# EASYEDA.net
KiCad netlist of a schematic drawn in EasyEDA
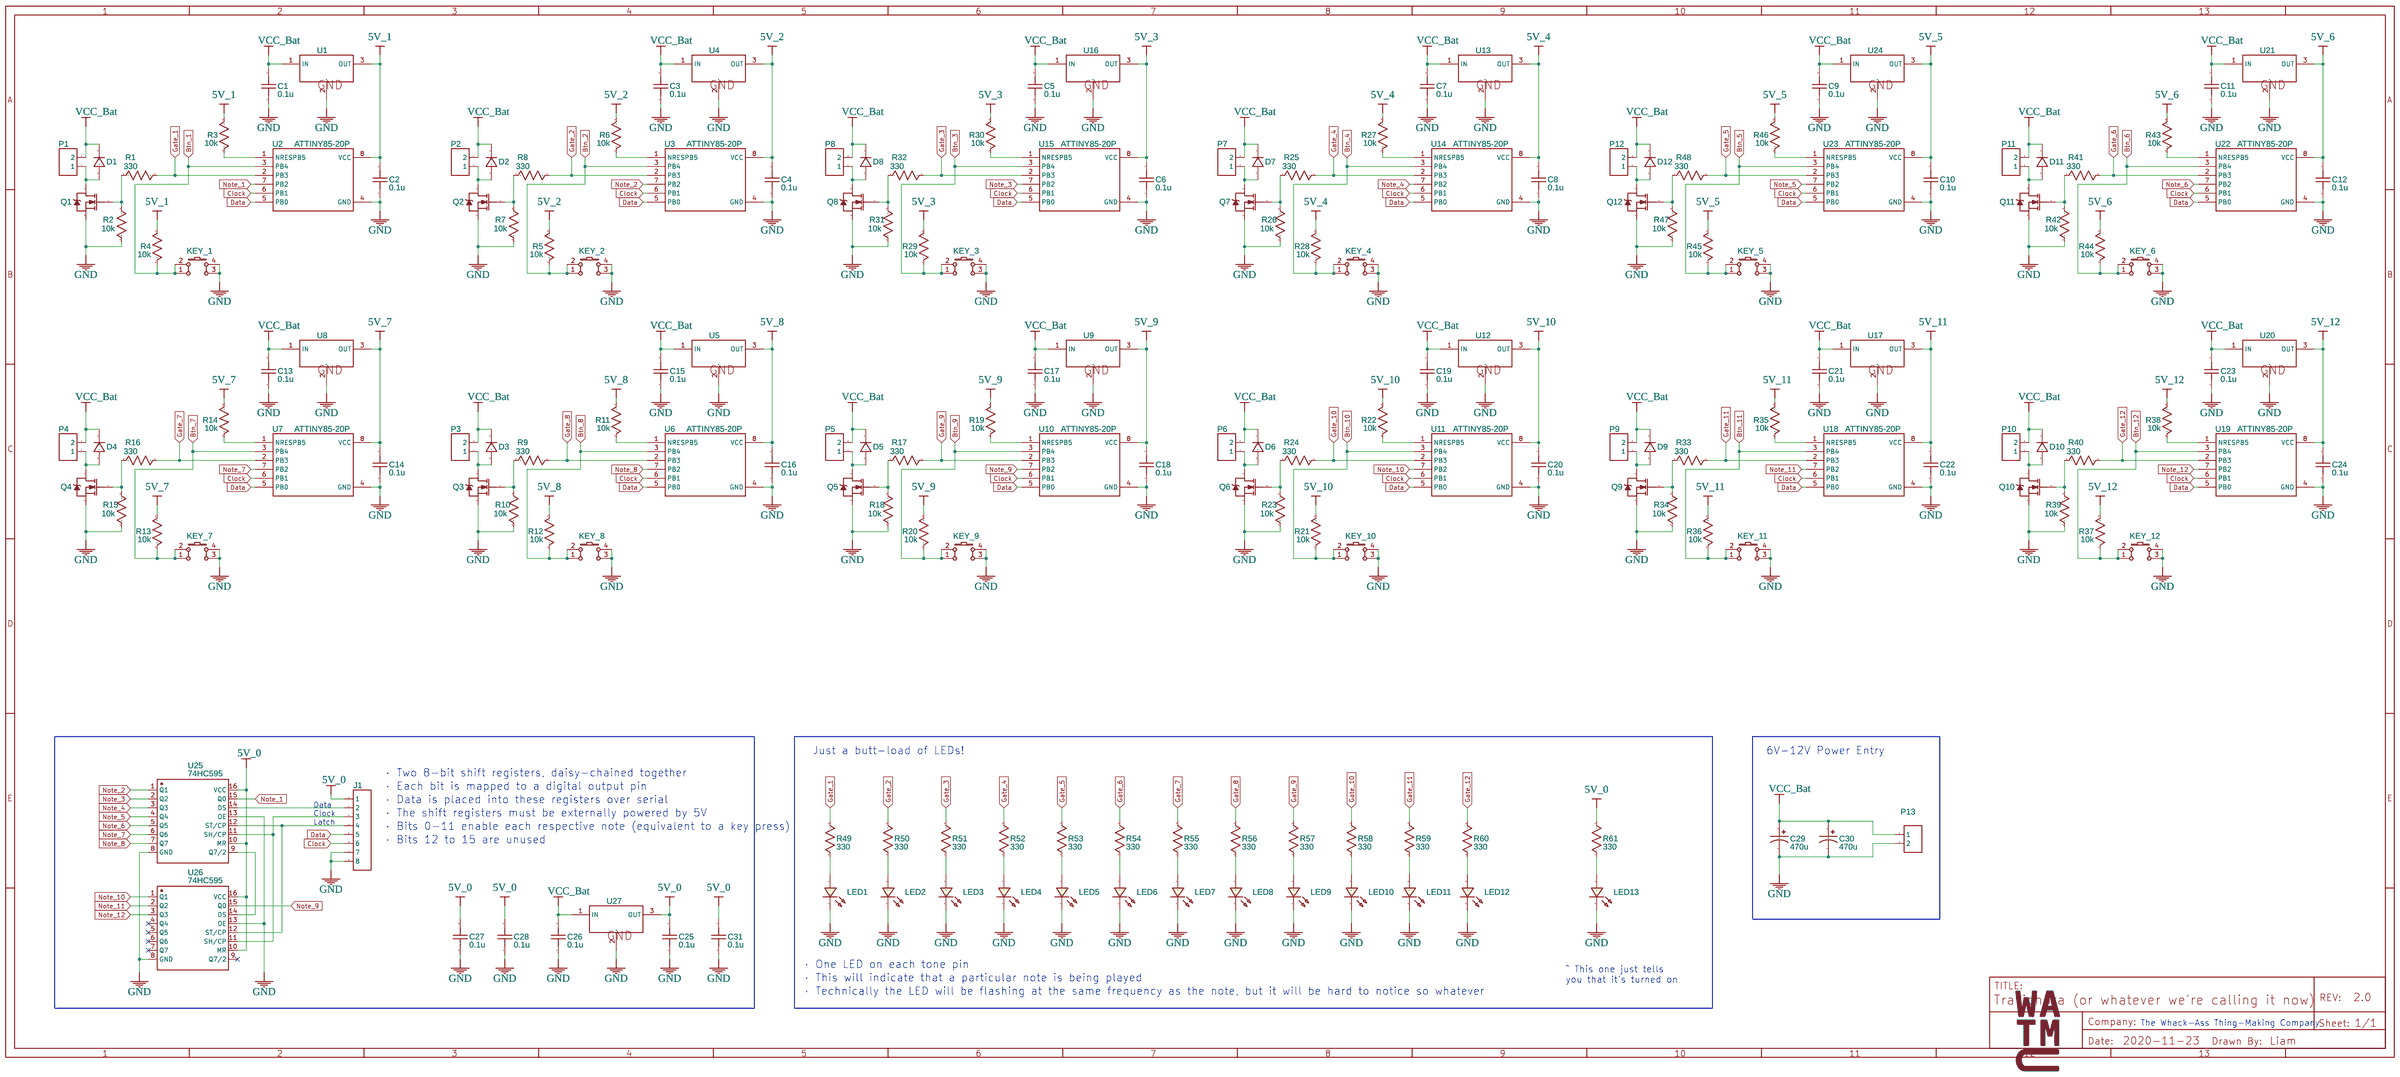
[diagram p0: schematic sheet]

(export (version "E")
  (design (tool "Eeschema 10.0.6"))
  (components
    (comp (ref "C1") (value "0.1u") (libsource (lib "") (part "C_1206_US")))
    (comp (ref "C2") (value "0.1u") (libsource (lib "") (part "C_1206_US")))
    (comp (ref "C3") (value "0.1u") (libsource (lib "") (part "C_1206_US")))
    (comp (ref "C4") (value "0.1u") (libsource (lib "") (part "C_1206_US")))
    (comp (ref "C5") (value "0.1u") (libsource (lib "") (part "C_1206_US")))
    (comp (ref "C6") (value "0.1u") (libsource (lib "") (part "C_1206_US")))
    (comp (ref "C7") (value "0.1u") (libsource (lib "") (part "C_1206_US")))
    (comp (ref "C8") (value "0.1u") (libsource (lib "") (part "C_1206_US")))
    (comp (ref "C9") (value "0.1u") (libsource (lib "") (part "C_1206_US")))
    (comp (ref "C10") (value "0.1u") (libsource (lib "") (part "C_1206_US")))
    (comp (ref "C11") (value "0.1u") (libsource (lib "") (part "C_1206_US")))
    (comp (ref "C12") (value "0.1u") (libsource (lib "") (part "C_1206_US")))
    (comp (ref "C13") (value "0.1u") (libsource (lib "") (part "C_1206_US")))
    (comp (ref "C14") (value "0.1u") (libsource (lib "") (part "C_1206_US")))
    (comp (ref "C15") (value "0.1u") (libsource (lib "") (part "C_1206_US")))
    (comp (ref "C16") (value "0.1u") (libsource (lib "") (part "C_1206_US")))
    (comp (ref "C17") (value "0.1u") (libsource (lib "") (part "C_1206_US")))
    (comp (ref "C18") (value "0.1u") (libsource (lib "") (part "C_1206_US")))
    (comp (ref "C19") (value "0.1u") (libsource (lib "") (part "C_1206_US")))
    (comp (ref "C20") (value "0.1u") (libsource (lib "") (part "C_1206_US")))
    (comp (ref "C21") (value "0.1u") (libsource (lib "") (part "C_1206_US")))
    (comp (ref "C22") (value "0.1u") (libsource (lib "") (part "C_1206_US")))
    (comp (ref "C23") (value "0.1u") (libsource (lib "") (part "C_1206_US")))
    (comp (ref "C24") (value "0.1u") (libsource (lib "") (part "C_1206_US")))
    (comp (ref "C25") (value "0.1u") (libsource (lib "") (part "C_1206_US")))
    (comp (ref "C26") (value "0.1u") (libsource (lib "") (part "C_1206_US")))
    (comp (ref "C27") (value "0.1u") (libsource (lib "") (part "C_1206_US")))
    (comp (ref "C28") (value "0.1u") (libsource (lib "") (part "C_1206_US")))
    (comp (ref "C29") (value "470u") (libsource (lib "") (part "CE_TH_D10.0×F5.0_US")))
    (comp (ref "C30") (value "470u") (libsource (lib "") (part "CE_TH_D10.0×F5.0_US")))
    (comp (ref "C31") (value "0.1u") (libsource (lib "") (part "C_1206_US")))
    (comp (ref "D1")
      (value "1N4007")
      (fields (field (name "BOM_Supplier Part") "C106903"))
      (libsource (lib "") (part "1N4007"))
    )
    (comp (ref "D2")
      (value "1N4007")
      (fields (field (name "BOM_Supplier Part") "C106903"))
      (libsource (lib "") (part "1N4007"))
    )
    (comp (ref "D3")
      (value "1N4007")
      (fields (field (name "BOM_Supplier Part") "C106903"))
      (libsource (lib "") (part "1N4007"))
    )
    (comp (ref "D4")
      (value "1N4007")
      (fields (field (name "BOM_Supplier Part") "C106903"))
      (libsource (lib "") (part "1N4007"))
    )
    (comp (ref "D5")
      (value "1N4007")
      (fields (field (name "BOM_Supplier Part") "C106903"))
      (libsource (lib "") (part "1N4007"))
    )
    (comp (ref "D6")
      (value "1N4007")
      (fields (field (name "BOM_Supplier Part") "C106903"))
      (libsource (lib "") (part "1N4007"))
    )
    (comp (ref "D7")
      (value "1N4007")
      (fields (field (name "BOM_Supplier Part") "C106903"))
      (libsource (lib "") (part "1N4007"))
    )
    (comp (ref "D8")
      (value "1N4007")
      (fields (field (name "BOM_Supplier Part") "C106903"))
      (libsource (lib "") (part "1N4007"))
    )
    (comp (ref "D9")
      (value "1N4007")
      (fields (field (name "BOM_Supplier Part") "C106903"))
      (libsource (lib "") (part "1N4007"))
    )
    (comp (ref "D10")
      (value "1N4007")
      (fields (field (name "BOM_Supplier Part") "C106903"))
      (libsource (lib "") (part "1N4007"))
    )
    (comp (ref "D11")
      (value "1N4007")
      (fields (field (name "BOM_Supplier Part") "C106903"))
      (libsource (lib "") (part "1N4007"))
    )
    (comp (ref "D12")
      (value "1N4007")
      (fields (field (name "BOM_Supplier Part") "C106903"))
      (libsource (lib "") (part "1N4007"))
    )
    (comp (ref "J1")
      (value "HDR-M-2.54_1x8")
      (fields (field (name "BOM_Supplier Part") "C190820"))
      (libsource (lib "") (part "HDR-M-2.54_1x8"))
    )
    (comp (ref "KEY_1")
      (value "K4-6×6_TH")
      (fields
        (field (name "BOM_Manufacturer Part") "K2-1102DP-E4SW-04")
        (field (name "BOM_Supplier Part") "C136684")
      )
      (libsource (lib "") (part "K4-6×6_TH"))
    )
    (comp (ref "KEY_2")
      (value "K4-6×6_TH")
      (fields
        (field (name "BOM_Manufacturer Part") "K2-1102DP-E4SW-04")
        (field (name "BOM_Supplier Part") "C136684")
      )
      (libsource (lib "") (part "K4-6×6_TH"))
    )
    (comp (ref "KEY_3")
      (value "K4-6×6_TH")
      (fields
        (field (name "BOM_Manufacturer Part") "K2-1102DP-E4SW-04")
        (field (name "BOM_Supplier Part") "C136684")
      )
      (libsource (lib "") (part "K4-6×6_TH"))
    )
    (comp (ref "KEY_4")
      (value "K4-6×6_TH")
      (fields
        (field (name "BOM_Manufacturer Part") "K2-1102DP-E4SW-04")
        (field (name "BOM_Supplier Part") "C136684")
      )
      (libsource (lib "") (part "K4-6×6_TH"))
    )
    (comp (ref "KEY_5")
      (value "K4-6×6_TH")
      (fields
        (field (name "BOM_Manufacturer Part") "K2-1102DP-E4SW-04")
        (field (name "BOM_Supplier Part") "C136684")
      )
      (libsource (lib "") (part "K4-6×6_TH"))
    )
    (comp (ref "KEY_6")
      (value "K4-6×6_TH")
      (fields
        (field (name "BOM_Manufacturer Part") "K2-1102DP-E4SW-04")
        (field (name "BOM_Supplier Part") "C136684")
      )
      (libsource (lib "") (part "K4-6×6_TH"))
    )
    (comp (ref "KEY_7")
      (value "K4-6×6_TH")
      (fields
        (field (name "BOM_Manufacturer Part") "K2-1102DP-E4SW-04")
        (field (name "BOM_Supplier Part") "C136684")
      )
      (libsource (lib "") (part "K4-6×6_TH"))
    )
    (comp (ref "KEY_8")
      (value "K4-6×6_TH")
      (fields
        (field (name "BOM_Manufacturer Part") "K2-1102DP-E4SW-04")
        (field (name "BOM_Supplier Part") "C136684")
      )
      (libsource (lib "") (part "K4-6×6_TH"))
    )
    (comp (ref "KEY_9")
      (value "K4-6×6_TH")
      (fields
        (field (name "BOM_Manufacturer Part") "K2-1102DP-E4SW-04")
        (field (name "BOM_Supplier Part") "C136684")
      )
      (libsource (lib "") (part "K4-6×6_TH"))
    )
    (comp (ref "KEY_10")
      (value "K4-6×6_TH")
      (fields
        (field (name "BOM_Manufacturer Part") "K2-1102DP-E4SW-04")
        (field (name "BOM_Supplier Part") "C136684")
      )
      (libsource (lib "") (part "K4-6×6_TH"))
    )
    (comp (ref "KEY_11")
      (value "K4-6×6_TH")
      (fields
        (field (name "BOM_Manufacturer Part") "K2-1102DP-E4SW-04")
        (field (name "BOM_Supplier Part") "C136684")
      )
      (libsource (lib "") (part "K4-6×6_TH"))
    )
    (comp (ref "KEY_12")
      (value "K4-6×6_TH")
      (fields
        (field (name "BOM_Manufacturer Part") "K2-1102DP-E4SW-04")
        (field (name "BOM_Supplier Part") "C136684")
      )
      (libsource (lib "") (part "K4-6×6_TH"))
    )
    (comp (ref "LED1")
      (value "LED-TH-3mm_R")
      (fields
        (field (name "BOM_Manufacturer Part") "204-10SDRD/S530-A3-L")
        (field (name "BOM_Supplier Part") "C84774")
      )
      (libsource (lib "") (part "LED-TH-3mm_R"))
    )
    (comp (ref "LED2")
      (value "LED-TH-3mm_R")
      (fields
        (field (name "BOM_Manufacturer Part") "204-10SDRD/S530-A3-L")
        (field (name "BOM_Supplier Part") "C84774")
      )
      (libsource (lib "") (part "LED-TH-3mm_R"))
    )
    (comp (ref "LED3")
      (value "LED-TH-3mm_R")
      (fields
        (field (name "BOM_Manufacturer Part") "204-10SDRD/S530-A3-L")
        (field (name "BOM_Supplier Part") "C84774")
      )
      (libsource (lib "") (part "LED-TH-3mm_R"))
    )
    (comp (ref "LED4")
      (value "LED-TH-3mm_R")
      (fields
        (field (name "BOM_Manufacturer Part") "204-10SDRD/S530-A3-L")
        (field (name "BOM_Supplier Part") "C84774")
      )
      (libsource (lib "") (part "LED-TH-3mm_R"))
    )
    (comp (ref "LED5")
      (value "LED-TH-3mm_R")
      (fields
        (field (name "BOM_Manufacturer Part") "204-10SDRD/S530-A3-L")
        (field (name "BOM_Supplier Part") "C84774")
      )
      (libsource (lib "") (part "LED-TH-3mm_R"))
    )
    (comp (ref "LED6")
      (value "LED-TH-3mm_R")
      (fields
        (field (name "BOM_Manufacturer Part") "204-10SDRD/S530-A3-L")
        (field (name "BOM_Supplier Part") "C84774")
      )
      (libsource (lib "") (part "LED-TH-3mm_R"))
    )
    (comp (ref "LED7")
      (value "LED-TH-3mm_R")
      (fields
        (field (name "BOM_Manufacturer Part") "204-10SDRD/S530-A3-L")
        (field (name "BOM_Supplier Part") "C84774")
      )
      (libsource (lib "") (part "LED-TH-3mm_R"))
    )
    (comp (ref "LED8")
      (value "LED-TH-3mm_R")
      (fields
        (field (name "BOM_Manufacturer Part") "204-10SDRD/S530-A3-L")
        (field (name "BOM_Supplier Part") "C84774")
      )
      (libsource (lib "") (part "LED-TH-3mm_R"))
    )
    (comp (ref "LED9")
      (value "LED-TH-3mm_R")
      (fields
        (field (name "BOM_Manufacturer Part") "204-10SDRD/S530-A3-L")
        (field (name "BOM_Supplier Part") "C84774")
      )
      (libsource (lib "") (part "LED-TH-3mm_R"))
    )
    (comp (ref "LED10")
      (value "LED-TH-3mm_R")
      (fields
        (field (name "BOM_Manufacturer Part") "204-10SDRD/S530-A3-L")
        (field (name "BOM_Supplier Part") "C84774")
      )
      (libsource (lib "") (part "LED-TH-3mm_R"))
    )
    (comp (ref "LED11")
      (value "LED-TH-3mm_R")
      (fields
        (field (name "BOM_Manufacturer Part") "204-10SDRD/S530-A3-L")
        (field (name "BOM_Supplier Part") "C84774")
      )
      (libsource (lib "") (part "LED-TH-3mm_R"))
    )
    (comp (ref "LED12")
      (value "LED-TH-3mm_R")
      (fields
        (field (name "BOM_Manufacturer Part") "204-10SDRD/S530-A3-L")
        (field (name "BOM_Supplier Part") "C84774")
      )
      (libsource (lib "") (part "LED-TH-3mm_R"))
    )
    (comp (ref "LED13")
      (value "LED-TH-3mm_G")
      (fields
        (field (name "BOM_Manufacturer Part") "204-10SYGD/S530-E3")
        (field (name "BOM_Supplier Part") "C85161")
      )
      (libsource (lib "") (part "LED-TH-3mm_G"))
    )
    (comp (ref "P1") (value "Magnet 1") (libsource (lib "") (part "CONN-TH_2P-P5.00")))
    (comp (ref "P2") (value "Magnet 1") (libsource (lib "") (part "CONN-TH_2P-P5.00")))
    (comp (ref "P3") (value "Magnet 1") (libsource (lib "") (part "CONN-TH_2P-P5.00")))
    (comp (ref "P4") (value "Magnet 1") (libsource (lib "") (part "CONN-TH_2P-P5.00")))
    (comp (ref "P5") (value "Magnet 1") (libsource (lib "") (part "CONN-TH_2P-P5.00")))
    (comp (ref "P6") (value "Magnet 1") (libsource (lib "") (part "CONN-TH_2P-P5.00")))
    (comp (ref "P7") (value "Magnet 1") (libsource (lib "") (part "CONN-TH_2P-P5.00")))
    (comp (ref "P8") (value "Magnet 1") (libsource (lib "") (part "CONN-TH_2P-P5.00")))
    (comp (ref "P9") (value "Magnet 1") (libsource (lib "") (part "CONN-TH_2P-P5.00")))
    (comp (ref "P10") (value "Magnet 1") (libsource (lib "") (part "CONN-TH_2P-P5.00")))
    (comp (ref "P11") (value "Magnet 1") (libsource (lib "") (part "CONN-TH_2P-P5.00")))
    (comp (ref "P12") (value "Magnet 1") (libsource (lib "") (part "CONN-TH_2P-P5.00")))
    (comp (ref "P13") (value "Magnet 1") (libsource (lib "") (part "CONN-TH_2P-P5.00_1")))
    (comp (ref "Q1")
      (value "30N06L-TA3-T")
      (fields (field (name "BOM_Supplier Part") "C99961"))
      (libsource (lib "") (part "30N06L-TA3-T"))
    )
    (comp (ref "Q2")
      (value "30N06L-TA3-T")
      (fields (field (name "BOM_Supplier Part") "C99961"))
      (libsource (lib "") (part "30N06L-TA3-T"))
    )
    (comp (ref "Q3")
      (value "30N06L-TA3-T")
      (fields (field (name "BOM_Supplier Part") "C99961"))
      (libsource (lib "") (part "30N06L-TA3-T"))
    )
    (comp (ref "Q4")
      (value "30N06L-TA3-T")
      (fields (field (name "BOM_Supplier Part") "C99961"))
      (libsource (lib "") (part "30N06L-TA3-T"))
    )
    (comp (ref "Q5")
      (value "30N06L-TA3-T")
      (fields (field (name "BOM_Supplier Part") "C99961"))
      (libsource (lib "") (part "30N06L-TA3-T"))
    )
    (comp (ref "Q6")
      (value "30N06L-TA3-T")
      (fields (field (name "BOM_Supplier Part") "C99961"))
      (libsource (lib "") (part "30N06L-TA3-T"))
    )
    (comp (ref "Q7")
      (value "30N06L-TA3-T")
      (fields (field (name "BOM_Supplier Part") "C99961"))
      (libsource (lib "") (part "30N06L-TA3-T"))
    )
    (comp (ref "Q8")
      (value "30N06L-TA3-T")
      (fields (field (name "BOM_Supplier Part") "C99961"))
      (libsource (lib "") (part "30N06L-TA3-T"))
    )
    (comp (ref "Q9")
      (value "30N06L-TA3-T")
      (fields (field (name "BOM_Supplier Part") "C99961"))
      (libsource (lib "") (part "30N06L-TA3-T"))
    )
    (comp (ref "Q10")
      (value "30N06L-TA3-T")
      (fields (field (name "BOM_Supplier Part") "C99961"))
      (libsource (lib "") (part "30N06L-TA3-T"))
    )
    (comp (ref "Q11")
      (value "30N06L-TA3-T")
      (fields (field (name "BOM_Supplier Part") "C99961"))
      (libsource (lib "") (part "30N06L-TA3-T"))
    )
    (comp (ref "Q12")
      (value "30N06L-TA3-T")
      (fields (field (name "BOM_Supplier Part") "C99961"))
      (libsource (lib "") (part "30N06L-TA3-T"))
    )
    (comp (ref "R1") (value "330") (libsource (lib "") (part "R_AXIAL-0.3_US_2")))
    (comp (ref "R2") (value "10k") (libsource (lib "") (part "R_AXIAL-0.3_US")))
    (comp (ref "R3") (value "10k") (libsource (lib "") (part "R_AXIAL-0.3_US_1")))
    (comp (ref "R4") (value "10k") (libsource (lib "") (part "R_AXIAL-0.3_US_1")))
    (comp (ref "R5") (value "10k") (libsource (lib "") (part "R_AXIAL-0.3_US_1")))
    (comp (ref "R6") (value "10k") (libsource (lib "") (part "R_AXIAL-0.3_US_1")))
    (comp (ref "R7") (value "10k") (libsource (lib "") (part "R_AXIAL-0.3_US")))
    (comp (ref "R8") (value "330") (libsource (lib "") (part "R_AXIAL-0.3_US_2")))
    (comp (ref "R9") (value "330") (libsource (lib "") (part "R_AXIAL-0.3_US_2")))
    (comp (ref "R10") (value "10k") (libsource (lib "") (part "R_AXIAL-0.3_US")))
    (comp (ref "R11") (value "10k") (libsource (lib "") (part "R_AXIAL-0.3_US_1")))
    (comp (ref "R12") (value "10k") (libsource (lib "") (part "R_AXIAL-0.3_US_1")))
    (comp (ref "R13") (value "10k") (libsource (lib "") (part "R_AXIAL-0.3_US_1")))
    (comp (ref "R14") (value "10k") (libsource (lib "") (part "R_AXIAL-0.3_US_1")))
    (comp (ref "R15") (value "10k") (libsource (lib "") (part "R_AXIAL-0.3_US")))
    (comp (ref "R16") (value "330") (libsource (lib "") (part "R_AXIAL-0.3_US_2")))
    (comp (ref "R17") (value "330") (libsource (lib "") (part "R_AXIAL-0.3_US_2")))
    (comp (ref "R18") (value "10k") (libsource (lib "") (part "R_AXIAL-0.3_US")))
    (comp (ref "R19") (value "10k") (libsource (lib "") (part "R_AXIAL-0.3_US_1")))
    (comp (ref "R20") (value "10k") (libsource (lib "") (part "R_AXIAL-0.3_US_1")))
    (comp (ref "R21") (value "10k") (libsource (lib "") (part "R_AXIAL-0.3_US_1")))
    (comp (ref "R22") (value "10k") (libsource (lib "") (part "R_AXIAL-0.3_US_1")))
    (comp (ref "R23") (value "10k") (libsource (lib "") (part "R_AXIAL-0.3_US")))
    (comp (ref "R24") (value "330") (libsource (lib "") (part "R_AXIAL-0.3_US_2")))
    (comp (ref "R25") (value "330") (libsource (lib "") (part "R_AXIAL-0.3_US_2")))
    (comp (ref "R26") (value "10k") (libsource (lib "") (part "R_AXIAL-0.3_US")))
    (comp (ref "R27") (value "10k") (libsource (lib "") (part "R_AXIAL-0.3_US_1")))
    (comp (ref "R28") (value "10k") (libsource (lib "") (part "R_AXIAL-0.3_US_1")))
    (comp (ref "R29") (value "10k") (libsource (lib "") (part "R_AXIAL-0.3_US_1")))
    (comp (ref "R30") (value "10k") (libsource (lib "") (part "R_AXIAL-0.3_US_1")))
    (comp (ref "R31") (value "10k") (libsource (lib "") (part "R_AXIAL-0.3_US")))
    (comp (ref "R32") (value "330") (libsource (lib "") (part "R_AXIAL-0.3_US_2")))
    (comp (ref "R33") (value "330") (libsource (lib "") (part "R_AXIAL-0.3_US_2")))
    (comp (ref "R34") (value "10k") (libsource (lib "") (part "R_AXIAL-0.3_US")))
    (comp (ref "R35") (value "10k") (libsource (lib "") (part "R_AXIAL-0.3_US_1")))
    (comp (ref "R36") (value "10k") (libsource (lib "") (part "R_AXIAL-0.3_US_1")))
    (comp (ref "R37") (value "10k") (libsource (lib "") (part "R_AXIAL-0.3_US_1")))
    (comp (ref "R38") (value "10k") (libsource (lib "") (part "R_AXIAL-0.3_US_1")))
    (comp (ref "R39") (value "10k") (libsource (lib "") (part "R_AXIAL-0.3_US")))
    (comp (ref "R40") (value "330") (libsource (lib "") (part "R_AXIAL-0.3_US_2")))
    (comp (ref "R41") (value "330") (libsource (lib "") (part "R_AXIAL-0.3_US_2")))
    (comp (ref "R42") (value "10k") (libsource (lib "") (part "R_AXIAL-0.3_US")))
    (comp (ref "R43") (value "10k") (libsource (lib "") (part "R_AXIAL-0.3_US_1")))
    (comp (ref "R44") (value "10k") (libsource (lib "") (part "R_AXIAL-0.3_US_1")))
    (comp (ref "R45") (value "10k") (libsource (lib "") (part "R_AXIAL-0.3_US_1")))
    (comp (ref "R46") (value "10k") (libsource (lib "") (part "R_AXIAL-0.3_US_1")))
    (comp (ref "R47") (value "10k") (libsource (lib "") (part "R_AXIAL-0.3_US")))
    (comp (ref "R48") (value "330") (libsource (lib "") (part "R_AXIAL-0.3_US_2")))
    (comp (ref "R49") (value "330") (libsource (lib "") (part "R_AXIAL-0.3_US")))
    (comp (ref "R50") (value "330") (libsource (lib "") (part "R_AXIAL-0.3_US")))
    (comp (ref "R51") (value "330") (libsource (lib "") (part "R_AXIAL-0.3_US")))
    (comp (ref "R52") (value "330") (libsource (lib "") (part "R_AXIAL-0.3_US")))
    (comp (ref "R53") (value "330") (libsource (lib "") (part "R_AXIAL-0.3_US")))
    (comp (ref "R54") (value "330") (libsource (lib "") (part "R_AXIAL-0.3_US")))
    (comp (ref "R55") (value "330") (libsource (lib "") (part "R_AXIAL-0.3_US")))
    (comp (ref "R56") (value "330") (libsource (lib "") (part "R_AXIAL-0.3_US")))
    (comp (ref "R57") (value "330") (libsource (lib "") (part "R_AXIAL-0.3_US")))
    (comp (ref "R58") (value "330") (libsource (lib "") (part "R_AXIAL-0.3_US")))
    (comp (ref "R59") (value "330") (libsource (lib "") (part "R_AXIAL-0.3_US")))
    (comp (ref "R60") (value "330") (libsource (lib "") (part "R_AXIAL-0.3_US")))
    (comp (ref "R61") (value "330") (libsource (lib "") (part "R_AXIAL-0.3_US")))
    (comp (ref "U1")
      (value "7805(TO-220)")
      (fields (field (name "BOM_Manufacturer Part") "L7805CV-DG") (field (name "BOM_Supplier Part") "C3795"))
      (libsource (lib "") (part "7805(TO-220)"))
    )
    (comp (ref "U2") (value "ATTINY85-20P") (libsource (lib "") (part "ATTINY85-20P")))
    (comp (ref "U3") (value "ATTINY85-20P") (libsource (lib "") (part "ATTINY85-20P")))
    (comp (ref "U4")
      (value "7805(TO-220)")
      (fields (field (name "BOM_Manufacturer Part") "L7805CV-DG") (field (name "BOM_Supplier Part") "C3795"))
      (libsource (lib "") (part "7805(TO-220)"))
    )
    (comp (ref "U5")
      (value "7805(TO-220)")
      (fields (field (name "BOM_Manufacturer Part") "L7805CV-DG") (field (name "BOM_Supplier Part") "C3795"))
      (libsource (lib "") (part "7805(TO-220)"))
    )
    (comp (ref "U6") (value "ATTINY85-20P") (libsource (lib "") (part "ATTINY85-20P")))
    (comp (ref "U7") (value "ATTINY85-20P") (libsource (lib "") (part "ATTINY85-20P")))
    (comp (ref "U8")
      (value "7805(TO-220)")
      (fields (field (name "BOM_Manufacturer Part") "L7805CV-DG") (field (name "BOM_Supplier Part") "C3795"))
      (libsource (lib "") (part "7805(TO-220)"))
    )
    (comp (ref "U9")
      (value "7805(TO-220)")
      (fields (field (name "BOM_Manufacturer Part") "L7805CV-DG") (field (name "BOM_Supplier Part") "C3795"))
      (libsource (lib "") (part "7805(TO-220)"))
    )
    (comp (ref "U10") (value "ATTINY85-20P") (libsource (lib "") (part "ATTINY85-20P")))
    (comp (ref "U11") (value "ATTINY85-20P") (libsource (lib "") (part "ATTINY85-20P")))
    (comp (ref "U12")
      (value "7805(TO-220)")
      (fields (field (name "BOM_Manufacturer Part") "L7805CV-DG") (field (name "BOM_Supplier Part") "C3795"))
      (libsource (lib "") (part "7805(TO-220)"))
    )
    (comp (ref "U13")
      (value "7805(TO-220)")
      (fields (field (name "BOM_Manufacturer Part") "L7805CV-DG") (field (name "BOM_Supplier Part") "C3795"))
      (libsource (lib "") (part "7805(TO-220)"))
    )
    (comp (ref "U14") (value "ATTINY85-20P") (libsource (lib "") (part "ATTINY85-20P")))
    (comp (ref "U15") (value "ATTINY85-20P") (libsource (lib "") (part "ATTINY85-20P")))
    (comp (ref "U16")
      (value "7805(TO-220)")
      (fields (field (name "BOM_Manufacturer Part") "L7805CV-DG") (field (name "BOM_Supplier Part") "C3795"))
      (libsource (lib "") (part "7805(TO-220)"))
    )
    (comp (ref "U17")
      (value "7805(TO-220)")
      (fields (field (name "BOM_Manufacturer Part") "L7805CV-DG") (field (name "BOM_Supplier Part") "C3795"))
      (libsource (lib "") (part "7805(TO-220)"))
    )
    (comp (ref "U18") (value "ATTINY85-20P") (libsource (lib "") (part "ATTINY85-20P")))
    (comp (ref "U19") (value "ATTINY85-20P") (libsource (lib "") (part "ATTINY85-20P")))
    (comp (ref "U20")
      (value "7805(TO-220)")
      (fields (field (name "BOM_Manufacturer Part") "L7805CV-DG") (field (name "BOM_Supplier Part") "C3795"))
      (libsource (lib "") (part "7805(TO-220)"))
    )
    (comp (ref "U21")
      (value "7805(TO-220)")
      (fields (field (name "BOM_Manufacturer Part") "L7805CV-DG") (field (name "BOM_Supplier Part") "C3795"))
      (libsource (lib "") (part "7805(TO-220)"))
    )
    (comp (ref "U22") (value "ATTINY85-20P") (libsource (lib "") (part "ATTINY85-20P")))
    (comp (ref "U23") (value "ATTINY85-20P") (libsource (lib "") (part "ATTINY85-20P")))
    (comp (ref "U24")
      (value "7805(TO-220)")
      (fields (field (name "BOM_Manufacturer Part") "L7805CV-DG") (field (name "BOM_Supplier Part") "C3795"))
      (libsource (lib "") (part "7805(TO-220)"))
    )
    (comp (ref "U25") (value "74HC595") (libsource (lib "") (part "74HC595N,112")))
    (comp (ref "U26") (value "74HC595") (libsource (lib "") (part "74HC595N,112")))
    (comp (ref "U27")
      (value "7805(TO-220)")
      (fields (field (name "BOM_Manufacturer Part") "L7805CV-DG") (field (name "BOM_Supplier Part") "C3795"))
      (libsource (lib "") (part "7805(TO-220)"))
    )
  )
  (nets
    (net (code "1") (name "5V_0") (class "Default")
      (node (ref "C25") (pin "2") (pinfunction "2_2") (pintype "unspecified"))
      (node (ref "C27") (pin "2") (pinfunction "2_2") (pintype "unspecified"))
      (node (ref "C28") (pin "2") (pinfunction "2_2") (pintype "unspecified"))
      (node (ref "C31") (pin "2") (pinfunction "2_2") (pintype "unspecified"))
      (node (ref "J1") (pin "1") (pinfunction "1_1") (pintype "unspecified"))
      (node (ref "R61") (pin "2") (pinfunction "2_2") (pintype "unspecified"))
      (node (ref "U25") (pin "10") (pinfunction "MR_10") (pintype "unspecified"))
      (node (ref "U25") (pin "16") (pinfunction "VCC_16") (pintype "unspecified"))
      (node (ref "U26") (pin "10") (pinfunction "MR_10") (pintype "unspecified"))
      (node (ref "U26") (pin "16") (pinfunction "VCC_16") (pintype "unspecified"))
      (node (ref "U27") (pin "3") (pinfunction "OUT_3") (pintype "passive"))
    )
    (net (code "2") (name "5V_1") (class "Default")
      (node (ref "C2") (pin "2") (pinfunction "2_2") (pintype "unspecified"))
      (node (ref "R3") (pin "2") (pinfunction "2_2") (pintype "unspecified"))
      (node (ref "R4") (pin "2") (pinfunction "2_2") (pintype "unspecified"))
      (node (ref "U1") (pin "3") (pinfunction "OUT_3") (pintype "passive"))
      (node (ref "U2") (pin "8") (pinfunction "VCC_8") (pintype "passive"))
    )
    (net (code "3") (name "5V_2") (class "Default")
      (node (ref "C4") (pin "2") (pinfunction "2_2") (pintype "unspecified"))
      (node (ref "R5") (pin "2") (pinfunction "2_2") (pintype "unspecified"))
      (node (ref "R6") (pin "2") (pinfunction "2_2") (pintype "unspecified"))
      (node (ref "U3") (pin "8") (pinfunction "VCC_8") (pintype "passive"))
      (node (ref "U4") (pin "3") (pinfunction "OUT_3") (pintype "passive"))
    )
    (net (code "4") (name "5V_3") (class "Default")
      (node (ref "C6") (pin "2") (pinfunction "2_2") (pintype "unspecified"))
      (node (ref "R29") (pin "2") (pinfunction "2_2") (pintype "unspecified"))
      (node (ref "R30") (pin "2") (pinfunction "2_2") (pintype "unspecified"))
      (node (ref "U15") (pin "8") (pinfunction "VCC_8") (pintype "passive"))
      (node (ref "U16") (pin "3") (pinfunction "OUT_3") (pintype "passive"))
    )
    (net (code "5") (name "5V_4") (class "Default")
      (node (ref "C8") (pin "2") (pinfunction "2_2") (pintype "unspecified"))
      (node (ref "R27") (pin "2") (pinfunction "2_2") (pintype "unspecified"))
      (node (ref "R28") (pin "2") (pinfunction "2_2") (pintype "unspecified"))
      (node (ref "U13") (pin "3") (pinfunction "OUT_3") (pintype "passive"))
      (node (ref "U14") (pin "8") (pinfunction "VCC_8") (pintype "passive"))
    )
    (net (code "6") (name "5V_5") (class "Default")
      (node (ref "C10") (pin "2") (pinfunction "2_2") (pintype "unspecified"))
      (node (ref "R45") (pin "2") (pinfunction "2_2") (pintype "unspecified"))
      (node (ref "R46") (pin "2") (pinfunction "2_2") (pintype "unspecified"))
      (node (ref "U23") (pin "8") (pinfunction "VCC_8") (pintype "passive"))
      (node (ref "U24") (pin "3") (pinfunction "OUT_3") (pintype "passive"))
    )
    (net (code "7") (name "5V_6") (class "Default")
      (node (ref "C12") (pin "2") (pinfunction "2_2") (pintype "unspecified"))
      (node (ref "R43") (pin "2") (pinfunction "2_2") (pintype "unspecified"))
      (node (ref "R44") (pin "2") (pinfunction "2_2") (pintype "unspecified"))
      (node (ref "U21") (pin "3") (pinfunction "OUT_3") (pintype "passive"))
      (node (ref "U22") (pin "8") (pinfunction "VCC_8") (pintype "passive"))
    )
    (net (code "8") (name "5V_7") (class "Default")
      (node (ref "C14") (pin "2") (pinfunction "2_2") (pintype "unspecified"))
      (node (ref "R13") (pin "2") (pinfunction "2_2") (pintype "unspecified"))
      (node (ref "R14") (pin "2") (pinfunction "2_2") (pintype "unspecified"))
      (node (ref "U7") (pin "8") (pinfunction "VCC_8") (pintype "passive"))
      (node (ref "U8") (pin "3") (pinfunction "OUT_3") (pintype "passive"))
    )
    (net (code "9") (name "5V_8") (class "Default")
      (node (ref "C16") (pin "2") (pinfunction "2_2") (pintype "unspecified"))
      (node (ref "R11") (pin "2") (pinfunction "2_2") (pintype "unspecified"))
      (node (ref "R12") (pin "2") (pinfunction "2_2") (pintype "unspecified"))
      (node (ref "U5") (pin "3") (pinfunction "OUT_3") (pintype "passive"))
      (node (ref "U6") (pin "8") (pinfunction "VCC_8") (pintype "passive"))
    )
    (net (code "10") (name "5V_9") (class "Default")
      (node (ref "C18") (pin "2") (pinfunction "2_2") (pintype "unspecified"))
      (node (ref "R19") (pin "2") (pinfunction "2_2") (pintype "unspecified"))
      (node (ref "R20") (pin "2") (pinfunction "2_2") (pintype "unspecified"))
      (node (ref "U10") (pin "8") (pinfunction "VCC_8") (pintype "passive"))
      (node (ref "U9") (pin "3") (pinfunction "OUT_3") (pintype "passive"))
    )
    (net (code "11") (name "5V_10") (class "Default")
      (node (ref "C20") (pin "2") (pinfunction "2_2") (pintype "unspecified"))
      (node (ref "R21") (pin "2") (pinfunction "2_2") (pintype "unspecified"))
      (node (ref "R22") (pin "2") (pinfunction "2_2") (pintype "unspecified"))
      (node (ref "U11") (pin "8") (pinfunction "VCC_8") (pintype "passive"))
      (node (ref "U12") (pin "3") (pinfunction "OUT_3") (pintype "passive"))
    )
    (net (code "12") (name "5V_11") (class "Default")
      (node (ref "C22") (pin "2") (pinfunction "2_2") (pintype "unspecified"))
      (node (ref "R35") (pin "2") (pinfunction "2_2") (pintype "unspecified"))
      (node (ref "R36") (pin "2") (pinfunction "2_2") (pintype "unspecified"))
      (node (ref "U17") (pin "3") (pinfunction "OUT_3") (pintype "passive"))
      (node (ref "U18") (pin "8") (pinfunction "VCC_8") (pintype "passive"))
    )
    (net (code "13") (name "5V_12") (class "Default")
      (node (ref "C24") (pin "2") (pinfunction "2_2") (pintype "unspecified"))
      (node (ref "R37") (pin "2") (pinfunction "2_2") (pintype "unspecified"))
      (node (ref "R38") (pin "2") (pinfunction "2_2") (pintype "unspecified"))
      (node (ref "U19") (pin "8") (pinfunction "VCC_8") (pintype "passive"))
      (node (ref "U20") (pin "3") (pinfunction "OUT_3") (pintype "passive"))
    )
    (net (code "14") (name "Btn_1") (class "Default")
      (node (ref "KEY_1") (pin "1") (pinfunction "1_1") (pintype "unspecified"))
      (node (ref "KEY_1") (pin "2") (pinfunction "2_2") (pintype "unspecified"))
      (node (ref "R4") (pin "1") (pinfunction "1_1") (pintype "unspecified"))
      (node (ref "U2") (pin "3") (pinfunction "PB4_3") (pintype "unspecified"))
    )
    (net (code "15") (name "Btn_2") (class "Default")
      (node (ref "KEY_2") (pin "1") (pinfunction "1_1") (pintype "unspecified"))
      (node (ref "KEY_2") (pin "2") (pinfunction "2_2") (pintype "unspecified"))
      (node (ref "R5") (pin "1") (pinfunction "1_1") (pintype "unspecified"))
      (node (ref "U3") (pin "3") (pinfunction "PB4_3") (pintype "unspecified"))
    )
    (net (code "16") (name "Btn_3") (class "Default")
      (node (ref "KEY_3") (pin "1") (pinfunction "1_1") (pintype "unspecified"))
      (node (ref "KEY_3") (pin "2") (pinfunction "2_2") (pintype "unspecified"))
      (node (ref "R29") (pin "1") (pinfunction "1_1") (pintype "unspecified"))
      (node (ref "U15") (pin "3") (pinfunction "PB4_3") (pintype "unspecified"))
    )
    (net (code "17") (name "Btn_4") (class "Default")
      (node (ref "KEY_4") (pin "1") (pinfunction "1_1") (pintype "unspecified"))
      (node (ref "KEY_4") (pin "2") (pinfunction "2_2") (pintype "unspecified"))
      (node (ref "R28") (pin "1") (pinfunction "1_1") (pintype "unspecified"))
      (node (ref "U14") (pin "3") (pinfunction "PB4_3") (pintype "unspecified"))
    )
    (net (code "18") (name "Btn_5") (class "Default")
      (node (ref "KEY_5") (pin "1") (pinfunction "1_1") (pintype "unspecified"))
      (node (ref "KEY_5") (pin "2") (pinfunction "2_2") (pintype "unspecified"))
      (node (ref "R45") (pin "1") (pinfunction "1_1") (pintype "unspecified"))
      (node (ref "U23") (pin "3") (pinfunction "PB4_3") (pintype "unspecified"))
    )
    (net (code "19") (name "Btn_6") (class "Default")
      (node (ref "KEY_6") (pin "1") (pinfunction "1_1") (pintype "unspecified"))
      (node (ref "KEY_6") (pin "2") (pinfunction "2_2") (pintype "unspecified"))
      (node (ref "R44") (pin "1") (pinfunction "1_1") (pintype "unspecified"))
      (node (ref "U22") (pin "3") (pinfunction "PB4_3") (pintype "unspecified"))
    )
    (net (code "20") (name "Btn_7") (class "Default")
      (node (ref "KEY_7") (pin "1") (pinfunction "1_1") (pintype "unspecified"))
      (node (ref "KEY_7") (pin "2") (pinfunction "2_2") (pintype "unspecified"))
      (node (ref "R13") (pin "1") (pinfunction "1_1") (pintype "unspecified"))
      (node (ref "U7") (pin "3") (pinfunction "PB4_3") (pintype "unspecified"))
    )
    (net (code "21") (name "Btn_8") (class "Default")
      (node (ref "KEY_8") (pin "1") (pinfunction "1_1") (pintype "unspecified"))
      (node (ref "KEY_8") (pin "2") (pinfunction "2_2") (pintype "unspecified"))
      (node (ref "R12") (pin "1") (pinfunction "1_1") (pintype "unspecified"))
      (node (ref "U6") (pin "3") (pinfunction "PB4_3") (pintype "unspecified"))
    )
    (net (code "22") (name "Btn_9") (class "Default")
      (node (ref "KEY_9") (pin "1") (pinfunction "1_1") (pintype "unspecified"))
      (node (ref "KEY_9") (pin "2") (pinfunction "2_2") (pintype "unspecified"))
      (node (ref "R20") (pin "1") (pinfunction "1_1") (pintype "unspecified"))
      (node (ref "U10") (pin "3") (pinfunction "PB4_3") (pintype "unspecified"))
    )
    (net (code "23") (name "Btn_10") (class "Default")
      (node (ref "KEY_10") (pin "1") (pinfunction "1_1") (pintype "unspecified"))
      (node (ref "KEY_10") (pin "2") (pinfunction "2_2") (pintype "unspecified"))
      (node (ref "R21") (pin "1") (pinfunction "1_1") (pintype "unspecified"))
      (node (ref "U11") (pin "3") (pinfunction "PB4_3") (pintype "unspecified"))
    )
    (net (code "24") (name "Btn_11") (class "Default")
      (node (ref "KEY_11") (pin "1") (pinfunction "1_1") (pintype "unspecified"))
      (node (ref "KEY_11") (pin "2") (pinfunction "2_2") (pintype "unspecified"))
      (node (ref "R36") (pin "1") (pinfunction "1_1") (pintype "unspecified"))
      (node (ref "U18") (pin "3") (pinfunction "PB4_3") (pintype "unspecified"))
    )
    (net (code "25") (name "Btn_12") (class "Default")
      (node (ref "KEY_12") (pin "1") (pinfunction "1_1") (pintype "unspecified"))
      (node (ref "KEY_12") (pin "2") (pinfunction "2_2") (pintype "unspecified"))
      (node (ref "R37") (pin "1") (pinfunction "1_1") (pintype "unspecified"))
      (node (ref "U19") (pin "3") (pinfunction "PB4_3") (pintype "unspecified"))
    )
    (net (code "26") (name "Clock") (class "Default")
      (node (ref "J1") (pin "6") (pinfunction "6_6") (pintype "unspecified"))
      (node (ref "U10") (pin "6") (pinfunction "PB1_6") (pintype "unspecified"))
      (node (ref "U11") (pin "6") (pinfunction "PB1_6") (pintype "unspecified"))
      (node (ref "U14") (pin "6") (pinfunction "PB1_6") (pintype "unspecified"))
      (node (ref "U15") (pin "6") (pinfunction "PB1_6") (pintype "unspecified"))
      (node (ref "U18") (pin "6") (pinfunction "PB1_6") (pintype "unspecified"))
      (node (ref "U19") (pin "6") (pinfunction "PB1_6") (pintype "unspecified"))
      (node (ref "U2") (pin "6") (pinfunction "PB1_6") (pintype "unspecified"))
      (node (ref "U22") (pin "6") (pinfunction "PB1_6") (pintype "unspecified"))
      (node (ref "U23") (pin "6") (pinfunction "PB1_6") (pintype "unspecified"))
      (node (ref "U3") (pin "6") (pinfunction "PB1_6") (pintype "unspecified"))
      (node (ref "U6") (pin "6") (pinfunction "PB1_6") (pintype "unspecified"))
      (node (ref "U7") (pin "6") (pinfunction "PB1_6") (pintype "unspecified"))
    )
    (net (code "27") (name "Data") (class "Default")
      (node (ref "J1") (pin "5") (pinfunction "5_5") (pintype "unspecified"))
      (node (ref "U10") (pin "5") (pinfunction "PB0_5") (pintype "unspecified"))
      (node (ref "U11") (pin "5") (pinfunction "PB0_5") (pintype "unspecified"))
      (node (ref "U14") (pin "5") (pinfunction "PB0_5") (pintype "unspecified"))
      (node (ref "U15") (pin "5") (pinfunction "PB0_5") (pintype "unspecified"))
      (node (ref "U18") (pin "5") (pinfunction "PB0_5") (pintype "unspecified"))
      (node (ref "U19") (pin "5") (pinfunction "PB0_5") (pintype "unspecified"))
      (node (ref "U2") (pin "5") (pinfunction "PB0_5") (pintype "unspecified"))
      (node (ref "U22") (pin "5") (pinfunction "PB0_5") (pintype "unspecified"))
      (node (ref "U23") (pin "5") (pinfunction "PB0_5") (pintype "unspecified"))
      (node (ref "U3") (pin "5") (pinfunction "PB0_5") (pintype "unspecified"))
      (node (ref "U6") (pin "5") (pinfunction "PB0_5") (pintype "unspecified"))
      (node (ref "U7") (pin "5") (pinfunction "PB0_5") (pintype "unspecified"))
    )
    (net (code "28") (name "GND") (class "Default")
      (node (ref "C1") (pin "1") (pinfunction "1_1") (pintype "unspecified"))
      (node (ref "C10") (pin "1") (pinfunction "1_1") (pintype "unspecified"))
      (node (ref "C11") (pin "1") (pinfunction "1_1") (pintype "unspecified"))
      (node (ref "C12") (pin "1") (pinfunction "1_1") (pintype "unspecified"))
      (node (ref "C13") (pin "1") (pinfunction "1_1") (pintype "unspecified"))
      (node (ref "C14") (pin "1") (pinfunction "1_1") (pintype "unspecified"))
      (node (ref "C15") (pin "1") (pinfunction "1_1") (pintype "unspecified"))
      (node (ref "C16") (pin "1") (pinfunction "1_1") (pintype "unspecified"))
      (node (ref "C17") (pin "1") (pinfunction "1_1") (pintype "unspecified"))
      (node (ref "C18") (pin "1") (pinfunction "1_1") (pintype "unspecified"))
      (node (ref "C19") (pin "1") (pinfunction "1_1") (pintype "unspecified"))
      (node (ref "C2") (pin "1") (pinfunction "1_1") (pintype "unspecified"))
      (node (ref "C20") (pin "1") (pinfunction "1_1") (pintype "unspecified"))
      (node (ref "C21") (pin "1") (pinfunction "1_1") (pintype "unspecified"))
      (node (ref "C22") (pin "1") (pinfunction "1_1") (pintype "unspecified"))
      (node (ref "C23") (pin "1") (pinfunction "1_1") (pintype "unspecified"))
      (node (ref "C24") (pin "1") (pinfunction "1_1") (pintype "unspecified"))
      (node (ref "C25") (pin "1") (pinfunction "1_1") (pintype "unspecified"))
      (node (ref "C26") (pin "1") (pinfunction "1_1") (pintype "unspecified"))
      (node (ref "C27") (pin "1") (pinfunction "1_1") (pintype "unspecified"))
      (node (ref "C28") (pin "1") (pinfunction "1_1") (pintype "unspecified"))
      (node (ref "C29") (pin "2") (pinfunction "2_2") (pintype "unspecified"))
      (node (ref "C3") (pin "1") (pinfunction "1_1") (pintype "unspecified"))
      (node (ref "C30") (pin "2") (pinfunction "2_2") (pintype "unspecified"))
      (node (ref "C31") (pin "1") (pinfunction "1_1") (pintype "unspecified"))
      (node (ref "C4") (pin "1") (pinfunction "1_1") (pintype "unspecified"))
      (node (ref "C5") (pin "1") (pinfunction "1_1") (pintype "unspecified"))
      (node (ref "C6") (pin "1") (pinfunction "1_1") (pintype "unspecified"))
      (node (ref "C7") (pin "1") (pinfunction "1_1") (pintype "unspecified"))
      (node (ref "C8") (pin "1") (pinfunction "1_1") (pintype "unspecified"))
      (node (ref "C9") (pin "1") (pinfunction "1_1") (pintype "unspecified"))
      (node (ref "J1") (pin "7") (pinfunction "7_7") (pintype "unspecified"))
      (node (ref "J1") (pin "8") (pinfunction "8_8") (pintype "unspecified"))
      (node (ref "KEY_1") (pin "3") (pinfunction "3_3") (pintype "unspecified"))
      (node (ref "KEY_1") (pin "4") (pinfunction "4_4") (pintype "unspecified"))
      (node (ref "KEY_10") (pin "3") (pinfunction "3_3") (pintype "unspecified"))
      (node (ref "KEY_10") (pin "4") (pinfunction "4_4") (pintype "unspecified"))
      (node (ref "KEY_11") (pin "3") (pinfunction "3_3") (pintype "unspecified"))
      (node (ref "KEY_11") (pin "4") (pinfunction "4_4") (pintype "unspecified"))
      (node (ref "KEY_12") (pin "3") (pinfunction "3_3") (pintype "unspecified"))
      (node (ref "KEY_12") (pin "4") (pinfunction "4_4") (pintype "unspecified"))
      (node (ref "KEY_2") (pin "3") (pinfunction "3_3") (pintype "unspecified"))
      (node (ref "KEY_2") (pin "4") (pinfunction "4_4") (pintype "unspecified"))
      (node (ref "KEY_3") (pin "3") (pinfunction "3_3") (pintype "unspecified"))
      (node (ref "KEY_3") (pin "4") (pinfunction "4_4") (pintype "unspecified"))
      (node (ref "KEY_4") (pin "3") (pinfunction "3_3") (pintype "unspecified"))
      (node (ref "KEY_4") (pin "4") (pinfunction "4_4") (pintype "unspecified"))
      (node (ref "KEY_5") (pin "3") (pinfunction "3_3") (pintype "unspecified"))
      (node (ref "KEY_5") (pin "4") (pinfunction "4_4") (pintype "unspecified"))
      (node (ref "KEY_6") (pin "3") (pinfunction "3_3") (pintype "unspecified"))
      (node (ref "KEY_6") (pin "4") (pinfunction "4_4") (pintype "unspecified"))
      (node (ref "KEY_7") (pin "3") (pinfunction "3_3") (pintype "unspecified"))
      (node (ref "KEY_7") (pin "4") (pinfunction "4_4") (pintype "unspecified"))
      (node (ref "KEY_8") (pin "3") (pinfunction "3_3") (pintype "unspecified"))
      (node (ref "KEY_8") (pin "4") (pinfunction "4_4") (pintype "unspecified"))
      (node (ref "KEY_9") (pin "3") (pinfunction "3_3") (pintype "unspecified"))
      (node (ref "KEY_9") (pin "4") (pinfunction "4_4") (pintype "unspecified"))
      (node (ref "LED1") (pin "2") (pinfunction "2_2") (pintype "unspecified"))
      (node (ref "LED10") (pin "2") (pinfunction "2_2") (pintype "unspecified"))
      (node (ref "LED11") (pin "2") (pinfunction "2_2") (pintype "unspecified"))
      (node (ref "LED12") (pin "2") (pinfunction "2_2") (pintype "unspecified"))
      (node (ref "LED13") (pin "2") (pinfunction "2_2") (pintype "unspecified"))
      (node (ref "LED2") (pin "2") (pinfunction "2_2") (pintype "unspecified"))
      (node (ref "LED3") (pin "2") (pinfunction "2_2") (pintype "unspecified"))
      (node (ref "LED4") (pin "2") (pinfunction "2_2") (pintype "unspecified"))
      (node (ref "LED5") (pin "2") (pinfunction "2_2") (pintype "unspecified"))
      (node (ref "LED6") (pin "2") (pinfunction "2_2") (pintype "unspecified"))
      (node (ref "LED7") (pin "2") (pinfunction "2_2") (pintype "unspecified"))
      (node (ref "LED8") (pin "2") (pinfunction "2_2") (pintype "unspecified"))
      (node (ref "LED9") (pin "2") (pinfunction "2_2") (pintype "unspecified"))
      (node (ref "P13") (pin "2") (pinfunction "2_2") (pintype "unspecified"))
      (node (ref "Q1") (pin "3") (pinfunction "S_3") (pintype "unspecified"))
      (node (ref "Q10") (pin "3") (pinfunction "S_3") (pintype "unspecified"))
      (node (ref "Q11") (pin "3") (pinfunction "S_3") (pintype "unspecified"))
      (node (ref "Q12") (pin "3") (pinfunction "S_3") (pintype "unspecified"))
      (node (ref "Q2") (pin "3") (pinfunction "S_3") (pintype "unspecified"))
      (node (ref "Q3") (pin "3") (pinfunction "S_3") (pintype "unspecified"))
      (node (ref "Q4") (pin "3") (pinfunction "S_3") (pintype "unspecified"))
      (node (ref "Q5") (pin "3") (pinfunction "S_3") (pintype "unspecified"))
      (node (ref "Q6") (pin "3") (pinfunction "S_3") (pintype "unspecified"))
      (node (ref "Q7") (pin "3") (pinfunction "S_3") (pintype "unspecified"))
      (node (ref "Q8") (pin "3") (pinfunction "S_3") (pintype "unspecified"))
      (node (ref "Q9") (pin "3") (pinfunction "S_3") (pintype "unspecified"))
      (node (ref "R10") (pin "1") (pinfunction "1_1") (pintype "unspecified"))
      (node (ref "R15") (pin "1") (pinfunction "1_1") (pintype "unspecified"))
      (node (ref "R18") (pin "1") (pinfunction "1_1") (pintype "unspecified"))
      (node (ref "R2") (pin "1") (pinfunction "1_1") (pintype "unspecified"))
      (node (ref "R23") (pin "1") (pinfunction "1_1") (pintype "unspecified"))
      (node (ref "R26") (pin "1") (pinfunction "1_1") (pintype "unspecified"))
      (node (ref "R31") (pin "1") (pinfunction "1_1") (pintype "unspecified"))
      (node (ref "R34") (pin "1") (pinfunction "1_1") (pintype "unspecified"))
      (node (ref "R39") (pin "1") (pinfunction "1_1") (pintype "unspecified"))
      (node (ref "R42") (pin "1") (pinfunction "1_1") (pintype "unspecified"))
      (node (ref "R47") (pin "1") (pinfunction "1_1") (pintype "unspecified"))
      (node (ref "R7") (pin "1") (pinfunction "1_1") (pintype "unspecified"))
      (node (ref "U1") (pin "2") (pinfunction "GND_2") (pintype "passive"))
      (node (ref "U10") (pin "4") (pinfunction "GND_4") (pintype "passive"))
      (node (ref "U11") (pin "4") (pinfunction "GND_4") (pintype "passive"))
      (node (ref "U12") (pin "2") (pinfunction "GND_2") (pintype "passive"))
      (node (ref "U13") (pin "2") (pinfunction "GND_2") (pintype "passive"))
      (node (ref "U14") (pin "4") (pinfunction "GND_4") (pintype "passive"))
      (node (ref "U15") (pin "4") (pinfunction "GND_4") (pintype "passive"))
      (node (ref "U16") (pin "2") (pinfunction "GND_2") (pintype "passive"))
      (node (ref "U17") (pin "2") (pinfunction "GND_2") (pintype "passive"))
      (node (ref "U18") (pin "4") (pinfunction "GND_4") (pintype "passive"))
      (node (ref "U19") (pin "4") (pinfunction "GND_4") (pintype "passive"))
      (node (ref "U2") (pin "4") (pinfunction "GND_4") (pintype "passive"))
      (node (ref "U20") (pin "2") (pinfunction "GND_2") (pintype "passive"))
      (node (ref "U21") (pin "2") (pinfunction "GND_2") (pintype "passive"))
      (node (ref "U22") (pin "4") (pinfunction "GND_4") (pintype "passive"))
      (node (ref "U23") (pin "4") (pinfunction "GND_4") (pintype "passive"))
      (node (ref "U24") (pin "2") (pinfunction "GND_2") (pintype "passive"))
      (node (ref "U25") (pin "13") (pinfunction "OE_13") (pintype "unspecified"))
      (node (ref "U25") (pin "8") (pinfunction "GND_8") (pintype "unspecified"))
      (node (ref "U26") (pin "13") (pinfunction "OE_13") (pintype "unspecified"))
      (node (ref "U26") (pin "8") (pinfunction "GND_8") (pintype "unspecified"))
      (node (ref "U27") (pin "2") (pinfunction "GND_2") (pintype "passive"))
      (node (ref "U3") (pin "4") (pinfunction "GND_4") (pintype "passive"))
      (node (ref "U4") (pin "2") (pinfunction "GND_2") (pintype "passive"))
      (node (ref "U5") (pin "2") (pinfunction "GND_2") (pintype "passive"))
      (node (ref "U6") (pin "4") (pinfunction "GND_4") (pintype "passive"))
      (node (ref "U7") (pin "4") (pinfunction "GND_4") (pintype "passive"))
      (node (ref "U8") (pin "2") (pinfunction "GND_2") (pintype "passive"))
      (node (ref "U9") (pin "2") (pinfunction "GND_2") (pintype "passive"))
    )
    (net (code "29") (name "Gate_1") (class "Default")
      (node (ref "R1") (pin "2") (pinfunction "2_2") (pintype "unspecified"))
      (node (ref "R49") (pin "2") (pinfunction "2_2") (pintype "unspecified"))
      (node (ref "U2") (pin "2") (pinfunction "PB3_2") (pintype "unspecified"))
    )
    (net (code "30") (name "Gate_2") (class "Default")
      (node (ref "R50") (pin "2") (pinfunction "2_2") (pintype "unspecified"))
      (node (ref "R8") (pin "2") (pinfunction "2_2") (pintype "unspecified"))
      (node (ref "U3") (pin "2") (pinfunction "PB3_2") (pintype "unspecified"))
    )
    (net (code "31") (name "Gate_3") (class "Default")
      (node (ref "R32") (pin "2") (pinfunction "2_2") (pintype "unspecified"))
      (node (ref "R51") (pin "2") (pinfunction "2_2") (pintype "unspecified"))
      (node (ref "U15") (pin "2") (pinfunction "PB3_2") (pintype "unspecified"))
    )
    (net (code "32") (name "Gate_4") (class "Default")
      (node (ref "R25") (pin "2") (pinfunction "2_2") (pintype "unspecified"))
      (node (ref "R52") (pin "2") (pinfunction "2_2") (pintype "unspecified"))
      (node (ref "U14") (pin "2") (pinfunction "PB3_2") (pintype "unspecified"))
    )
    (net (code "33") (name "Gate_5") (class "Default")
      (node (ref "R48") (pin "2") (pinfunction "2_2") (pintype "unspecified"))
      (node (ref "R53") (pin "2") (pinfunction "2_2") (pintype "unspecified"))
      (node (ref "U23") (pin "2") (pinfunction "PB3_2") (pintype "unspecified"))
    )
    (net (code "34") (name "Gate_6") (class "Default")
      (node (ref "R41") (pin "2") (pinfunction "2_2") (pintype "unspecified"))
      (node (ref "R54") (pin "2") (pinfunction "2_2") (pintype "unspecified"))
      (node (ref "U22") (pin "2") (pinfunction "PB3_2") (pintype "unspecified"))
    )
    (net (code "35") (name "Gate_7") (class "Default")
      (node (ref "R16") (pin "2") (pinfunction "2_2") (pintype "unspecified"))
      (node (ref "R55") (pin "2") (pinfunction "2_2") (pintype "unspecified"))
      (node (ref "U7") (pin "2") (pinfunction "PB3_2") (pintype "unspecified"))
    )
    (net (code "36") (name "Gate_8") (class "Default")
      (node (ref "R56") (pin "2") (pinfunction "2_2") (pintype "unspecified"))
      (node (ref "R9") (pin "2") (pinfunction "2_2") (pintype "unspecified"))
      (node (ref "U6") (pin "2") (pinfunction "PB3_2") (pintype "unspecified"))
    )
    (net (code "37") (name "Gate_9") (class "Default")
      (node (ref "R17") (pin "2") (pinfunction "2_2") (pintype "unspecified"))
      (node (ref "R57") (pin "2") (pinfunction "2_2") (pintype "unspecified"))
      (node (ref "U10") (pin "2") (pinfunction "PB3_2") (pintype "unspecified"))
    )
    (net (code "38") (name "Gate_10") (class "Default")
      (node (ref "R24") (pin "2") (pinfunction "2_2") (pintype "unspecified"))
      (node (ref "R58") (pin "2") (pinfunction "2_2") (pintype "unspecified"))
      (node (ref "U11") (pin "2") (pinfunction "PB3_2") (pintype "unspecified"))
    )
    (net (code "39") (name "Gate_11") (class "Default")
      (node (ref "R33") (pin "2") (pinfunction "2_2") (pintype "unspecified"))
      (node (ref "R59") (pin "2") (pinfunction "2_2") (pintype "unspecified"))
      (node (ref "U18") (pin "2") (pinfunction "PB3_2") (pintype "unspecified"))
    )
    (net (code "40") (name "Gate_12") (class "Default")
      (node (ref "R40") (pin "2") (pinfunction "2_2") (pintype "unspecified"))
      (node (ref "R60") (pin "2") (pinfunction "2_2") (pintype "unspecified"))
      (node (ref "U19") (pin "2") (pinfunction "PB3_2") (pintype "unspecified"))
    )
    (net (code "41") (name "Net-(LED1-Pad1)") (class "Default")
      (node (ref "LED1") (pin "1") (pinfunction "1_1") (pintype "unspecified"))
      (node (ref "R49") (pin "1") (pinfunction "1_1") (pintype "unspecified"))
    )
    (net (code "42") (name "Net-(LED2-Pad1)") (class "Default")
      (node (ref "LED2") (pin "1") (pinfunction "1_1") (pintype "unspecified"))
      (node (ref "R50") (pin "1") (pinfunction "1_1") (pintype "unspecified"))
    )
    (net (code "43") (name "Net-(LED3-Pad1)") (class "Default")
      (node (ref "LED3") (pin "1") (pinfunction "1_1") (pintype "unspecified"))
      (node (ref "R51") (pin "1") (pinfunction "1_1") (pintype "unspecified"))
    )
    (net (code "44") (name "Net-(LED4-Pad1)") (class "Default")
      (node (ref "LED4") (pin "1") (pinfunction "1_1") (pintype "unspecified"))
      (node (ref "R52") (pin "1") (pinfunction "1_1") (pintype "unspecified"))
    )
    (net (code "45") (name "Net-(LED5-Pad1)") (class "Default")
      (node (ref "LED5") (pin "1") (pinfunction "1_1") (pintype "unspecified"))
      (node (ref "R53") (pin "1") (pinfunction "1_1") (pintype "unspecified"))
    )
    (net (code "46") (name "Net-(LED6-Pad1)") (class "Default")
      (node (ref "LED6") (pin "1") (pinfunction "1_1") (pintype "unspecified"))
      (node (ref "R54") (pin "1") (pinfunction "1_1") (pintype "unspecified"))
    )
    (net (code "47") (name "Net-(LED7-Pad1)") (class "Default")
      (node (ref "LED7") (pin "1") (pinfunction "1_1") (pintype "unspecified"))
      (node (ref "R55") (pin "1") (pinfunction "1_1") (pintype "unspecified"))
    )
    (net (code "48") (name "Net-(LED8-Pad1)") (class "Default")
      (node (ref "LED8") (pin "1") (pinfunction "1_1") (pintype "unspecified"))
      (node (ref "R56") (pin "1") (pinfunction "1_1") (pintype "unspecified"))
    )
    (net (code "49") (name "Net-(LED9-Pad1)") (class "Default")
      (node (ref "LED9") (pin "1") (pinfunction "1_1") (pintype "unspecified"))
      (node (ref "R57") (pin "1") (pinfunction "1_1") (pintype "unspecified"))
    )
    (net (code "50") (name "Net-(LED10-Pad1)") (class "Default")
      (node (ref "LED10") (pin "1") (pinfunction "1_1") (pintype "unspecified"))
      (node (ref "R58") (pin "1") (pinfunction "1_1") (pintype "unspecified"))
    )
    (net (code "51") (name "Net-(LED11-Pad1)") (class "Default")
      (node (ref "LED11") (pin "1") (pinfunction "1_1") (pintype "unspecified"))
      (node (ref "R59") (pin "1") (pinfunction "1_1") (pintype "unspecified"))
    )
    (net (code "52") (name "Net-(LED12-Pad1)") (class "Default")
      (node (ref "LED12") (pin "1") (pinfunction "1_1") (pintype "unspecified"))
      (node (ref "R60") (pin "1") (pinfunction "1_1") (pintype "unspecified"))
    )
    (net (code "53") (name "Net-(LED13-Pad1)") (class "Default")
      (node (ref "LED13") (pin "1") (pinfunction "1_1") (pintype "unspecified"))
      (node (ref "R61") (pin "1") (pinfunction "1_1") (pintype "unspecified"))
    )
    (net (code "54") (name "Net-(Q1-D)") (class "Default")
      (node (ref "D1") (pin "2") (pinfunction "2_2") (pintype "unspecified"))
      (node (ref "P1") (pin "1") (pinfunction "1_1") (pintype "unspecified"))
      (node (ref "Q1") (pin "2") (pinfunction "D_2") (pintype "unspecified"))
    )
    (net (code "55") (name "Net-(Q1-G)") (class "Default")
      (node (ref "Q1") (pin "1") (pinfunction "G_1") (pintype "unspecified"))
      (node (ref "R1") (pin "1") (pinfunction "1_1") (pintype "unspecified"))
      (node (ref "R2") (pin "2") (pinfunction "2_2") (pintype "unspecified"))
    )
    (net (code "56") (name "Net-(Q2-D)") (class "Default")
      (node (ref "D2") (pin "2") (pinfunction "2_2") (pintype "unspecified"))
      (node (ref "P2") (pin "1") (pinfunction "1_1") (pintype "unspecified"))
      (node (ref "Q2") (pin "2") (pinfunction "D_2") (pintype "unspecified"))
    )
    (net (code "57") (name "Net-(Q2-G)") (class "Default")
      (node (ref "Q2") (pin "1") (pinfunction "G_1") (pintype "unspecified"))
      (node (ref "R7") (pin "2") (pinfunction "2_2") (pintype "unspecified"))
      (node (ref "R8") (pin "1") (pinfunction "1_1") (pintype "unspecified"))
    )
    (net (code "58") (name "Net-(Q3-D)") (class "Default")
      (node (ref "D3") (pin "2") (pinfunction "2_2") (pintype "unspecified"))
      (node (ref "P3") (pin "1") (pinfunction "1_1") (pintype "unspecified"))
      (node (ref "Q3") (pin "2") (pinfunction "D_2") (pintype "unspecified"))
    )
    (net (code "59") (name "Net-(Q3-G)") (class "Default")
      (node (ref "Q3") (pin "1") (pinfunction "G_1") (pintype "unspecified"))
      (node (ref "R10") (pin "2") (pinfunction "2_2") (pintype "unspecified"))
      (node (ref "R9") (pin "1") (pinfunction "1_1") (pintype "unspecified"))
    )
    (net (code "60") (name "Net-(Q4-D)") (class "Default")
      (node (ref "D4") (pin "2") (pinfunction "2_2") (pintype "unspecified"))
      (node (ref "P4") (pin "1") (pinfunction "1_1") (pintype "unspecified"))
      (node (ref "Q4") (pin "2") (pinfunction "D_2") (pintype "unspecified"))
    )
    (net (code "61") (name "Net-(Q4-G)") (class "Default")
      (node (ref "Q4") (pin "1") (pinfunction "G_1") (pintype "unspecified"))
      (node (ref "R15") (pin "2") (pinfunction "2_2") (pintype "unspecified"))
      (node (ref "R16") (pin "1") (pinfunction "1_1") (pintype "unspecified"))
    )
    (net (code "62") (name "Net-(Q5-D)") (class "Default")
      (node (ref "D5") (pin "2") (pinfunction "2_2") (pintype "unspecified"))
      (node (ref "P5") (pin "1") (pinfunction "1_1") (pintype "unspecified"))
      (node (ref "Q5") (pin "2") (pinfunction "D_2") (pintype "unspecified"))
    )
    (net (code "63") (name "Net-(Q5-G)") (class "Default")
      (node (ref "Q5") (pin "1") (pinfunction "G_1") (pintype "unspecified"))
      (node (ref "R17") (pin "1") (pinfunction "1_1") (pintype "unspecified"))
      (node (ref "R18") (pin "2") (pinfunction "2_2") (pintype "unspecified"))
    )
    (net (code "64") (name "Net-(Q6-D)") (class "Default")
      (node (ref "D6") (pin "2") (pinfunction "2_2") (pintype "unspecified"))
      (node (ref "P6") (pin "1") (pinfunction "1_1") (pintype "unspecified"))
      (node (ref "Q6") (pin "2") (pinfunction "D_2") (pintype "unspecified"))
    )
    (net (code "65") (name "Net-(Q6-G)") (class "Default")
      (node (ref "Q6") (pin "1") (pinfunction "G_1") (pintype "unspecified"))
      (node (ref "R23") (pin "2") (pinfunction "2_2") (pintype "unspecified"))
      (node (ref "R24") (pin "1") (pinfunction "1_1") (pintype "unspecified"))
    )
    (net (code "66") (name "Net-(Q7-D)") (class "Default")
      (node (ref "D7") (pin "2") (pinfunction "2_2") (pintype "unspecified"))
      (node (ref "P7") (pin "1") (pinfunction "1_1") (pintype "unspecified"))
      (node (ref "Q7") (pin "2") (pinfunction "D_2") (pintype "unspecified"))
    )
    (net (code "67") (name "Net-(Q7-G)") (class "Default")
      (node (ref "Q7") (pin "1") (pinfunction "G_1") (pintype "unspecified"))
      (node (ref "R25") (pin "1") (pinfunction "1_1") (pintype "unspecified"))
      (node (ref "R26") (pin "2") (pinfunction "2_2") (pintype "unspecified"))
    )
    (net (code "68") (name "Net-(Q8-D)") (class "Default")
      (node (ref "D8") (pin "2") (pinfunction "2_2") (pintype "unspecified"))
      (node (ref "P8") (pin "1") (pinfunction "1_1") (pintype "unspecified"))
      (node (ref "Q8") (pin "2") (pinfunction "D_2") (pintype "unspecified"))
    )
    (net (code "69") (name "Net-(Q8-G)") (class "Default")
      (node (ref "Q8") (pin "1") (pinfunction "G_1") (pintype "unspecified"))
      (node (ref "R31") (pin "2") (pinfunction "2_2") (pintype "unspecified"))
      (node (ref "R32") (pin "1") (pinfunction "1_1") (pintype "unspecified"))
    )
    (net (code "70") (name "Net-(Q9-D)") (class "Default")
      (node (ref "D9") (pin "2") (pinfunction "2_2") (pintype "unspecified"))
      (node (ref "P9") (pin "1") (pinfunction "1_1") (pintype "unspecified"))
      (node (ref "Q9") (pin "2") (pinfunction "D_2") (pintype "unspecified"))
    )
    (net (code "71") (name "Net-(Q9-G)") (class "Default")
      (node (ref "Q9") (pin "1") (pinfunction "G_1") (pintype "unspecified"))
      (node (ref "R33") (pin "1") (pinfunction "1_1") (pintype "unspecified"))
      (node (ref "R34") (pin "2") (pinfunction "2_2") (pintype "unspecified"))
    )
    (net (code "72") (name "Net-(Q10-D)") (class "Default")
      (node (ref "D10") (pin "2") (pinfunction "2_2") (pintype "unspecified"))
      (node (ref "P10") (pin "1") (pinfunction "1_1") (pintype "unspecified"))
      (node (ref "Q10") (pin "2") (pinfunction "D_2") (pintype "unspecified"))
    )
    (net (code "73") (name "Net-(Q10-G)") (class "Default")
      (node (ref "Q10") (pin "1") (pinfunction "G_1") (pintype "unspecified"))
      (node (ref "R39") (pin "2") (pinfunction "2_2") (pintype "unspecified"))
      (node (ref "R40") (pin "1") (pinfunction "1_1") (pintype "unspecified"))
    )
    (net (code "74") (name "Net-(Q11-D)") (class "Default")
      (node (ref "D11") (pin "2") (pinfunction "2_2") (pintype "unspecified"))
      (node (ref "P11") (pin "1") (pinfunction "1_1") (pintype "unspecified"))
      (node (ref "Q11") (pin "2") (pinfunction "D_2") (pintype "unspecified"))
    )
    (net (code "75") (name "Net-(Q11-G)") (class "Default")
      (node (ref "Q11") (pin "1") (pinfunction "G_1") (pintype "unspecified"))
      (node (ref "R41") (pin "1") (pinfunction "1_1") (pintype "unspecified"))
      (node (ref "R42") (pin "2") (pinfunction "2_2") (pintype "unspecified"))
    )
    (net (code "76") (name "Net-(Q12-D)") (class "Default")
      (node (ref "D12") (pin "2") (pinfunction "2_2") (pintype "unspecified"))
      (node (ref "P12") (pin "1") (pinfunction "1_1") (pintype "unspecified"))
      (node (ref "Q12") (pin "2") (pinfunction "D_2") (pintype "unspecified"))
    )
    (net (code "77") (name "Net-(Q12-G)") (class "Default")
      (node (ref "Q12") (pin "1") (pinfunction "G_1") (pintype "unspecified"))
      (node (ref "R47") (pin "2") (pinfunction "2_2") (pintype "unspecified"))
      (node (ref "R48") (pin "1") (pinfunction "1_1") (pintype "unspecified"))
    )
    (net (code "78") (name "Net-(U2-NRESPB5)") (class "Default")
      (node (ref "R3") (pin "1") (pinfunction "1_1") (pintype "unspecified"))
      (node (ref "U2") (pin "1") (pinfunction "NRESPB5_1") (pintype "unspecified"))
    )
    (net (code "79") (name "Net-(U3-NRESPB5)") (class "Default")
      (node (ref "R6") (pin "1") (pinfunction "1_1") (pintype "unspecified"))
      (node (ref "U3") (pin "1") (pinfunction "NRESPB5_1") (pintype "unspecified"))
    )
    (net (code "80") (name "Net-(U6-NRESPB5)") (class "Default")
      (node (ref "R11") (pin "1") (pinfunction "1_1") (pintype "unspecified"))
      (node (ref "U6") (pin "1") (pinfunction "NRESPB5_1") (pintype "unspecified"))
    )
    (net (code "81") (name "Net-(U7-NRESPB5)") (class "Default")
      (node (ref "R14") (pin "1") (pinfunction "1_1") (pintype "unspecified"))
      (node (ref "U7") (pin "1") (pinfunction "NRESPB5_1") (pintype "unspecified"))
    )
    (net (code "82") (name "Net-(U10-NRESPB5)") (class "Default")
      (node (ref "R19") (pin "1") (pinfunction "1_1") (pintype "unspecified"))
      (node (ref "U10") (pin "1") (pinfunction "NRESPB5_1") (pintype "unspecified"))
    )
    (net (code "83") (name "Net-(U11-NRESPB5)") (class "Default")
      (node (ref "R22") (pin "1") (pinfunction "1_1") (pintype "unspecified"))
      (node (ref "U11") (pin "1") (pinfunction "NRESPB5_1") (pintype "unspecified"))
    )
    (net (code "84") (name "Net-(U14-NRESPB5)") (class "Default")
      (node (ref "R27") (pin "1") (pinfunction "1_1") (pintype "unspecified"))
      (node (ref "U14") (pin "1") (pinfunction "NRESPB5_1") (pintype "unspecified"))
    )
    (net (code "85") (name "Net-(U15-NRESPB5)") (class "Default")
      (node (ref "R30") (pin "1") (pinfunction "1_1") (pintype "unspecified"))
      (node (ref "U15") (pin "1") (pinfunction "NRESPB5_1") (pintype "unspecified"))
    )
    (net (code "86") (name "Net-(U18-NRESPB5)") (class "Default")
      (node (ref "R35") (pin "1") (pinfunction "1_1") (pintype "unspecified"))
      (node (ref "U18") (pin "1") (pinfunction "NRESPB5_1") (pintype "unspecified"))
    )
    (net (code "87") (name "Net-(U19-NRESPB5)") (class "Default")
      (node (ref "R38") (pin "1") (pinfunction "1_1") (pintype "unspecified"))
      (node (ref "U19") (pin "1") (pinfunction "NRESPB5_1") (pintype "unspecified"))
    )
    (net (code "88") (name "Net-(U22-NRESPB5)") (class "Default")
      (node (ref "R43") (pin "1") (pinfunction "1_1") (pintype "unspecified"))
      (node (ref "U22") (pin "1") (pinfunction "NRESPB5_1") (pintype "unspecified"))
    )
    (net (code "89") (name "Net-(U23-NRESPB5)") (class "Default")
      (node (ref "R46") (pin "1") (pinfunction "1_1") (pintype "unspecified"))
      (node (ref "U23") (pin "1") (pinfunction "NRESPB5_1") (pintype "unspecified"))
    )
    (net (code "90") (name "Net-(U25-DS)") (class "Default")
      (node (ref "J1") (pin "2") (pinfunction "2_2") (pintype "unspecified"))
      (node (ref "U25") (pin "14") (pinfunction "DS_14") (pintype "unspecified"))
    )
    (net (code "91") (name "Net-(U25-Q7{slash}2)") (class "Default")
      (node (ref "U25") (pin "9") (pinfunction "Q7/2_9") (pintype "unspecified"))
      (node (ref "U26") (pin "14") (pinfunction "DS_14") (pintype "unspecified"))
    )
    (net (code "92") (name "Net-(U25-SH{slash}CP)") (class "Default")
      (node (ref "J1") (pin "3") (pinfunction "3_3") (pintype "unspecified"))
      (node (ref "U25") (pin "11") (pinfunction "SH/CP_11") (pintype "unspecified"))
      (node (ref "U26") (pin "11") (pinfunction "SH/CP_11") (pintype "unspecified"))
    )
    (net (code "93") (name "Net-(U25-ST{slash}CP)") (class "Default")
      (node (ref "J1") (pin "4") (pinfunction "4_4") (pintype "unspecified"))
      (node (ref "U25") (pin "12") (pinfunction "ST/CP_12") (pintype "unspecified"))
      (node (ref "U26") (pin "12") (pinfunction "ST/CP_12") (pintype "unspecified"))
    )
    (net (code "94") (name "Note_1") (class "Default")
      (node (ref "U2") (pin "7") (pinfunction "PB2_7") (pintype "unspecified"))
      (node (ref "U25") (pin "15") (pinfunction "Q0_15") (pintype "unspecified"))
    )
    (net (code "95") (name "Note_2") (class "Default")
      (node (ref "U25") (pin "1") (pinfunction "Q1_1") (pintype "unspecified"))
      (node (ref "U3") (pin "7") (pinfunction "PB2_7") (pintype "unspecified"))
    )
    (net (code "96") (name "Note_3") (class "Default")
      (node (ref "U15") (pin "7") (pinfunction "PB2_7") (pintype "unspecified"))
      (node (ref "U25") (pin "2") (pinfunction "Q2_2") (pintype "unspecified"))
    )
    (net (code "97") (name "Note_4") (class "Default")
      (node (ref "U14") (pin "7") (pinfunction "PB2_7") (pintype "unspecified"))
      (node (ref "U25") (pin "3") (pinfunction "Q3_3") (pintype "unspecified"))
    )
    (net (code "98") (name "Note_5") (class "Default")
      (node (ref "U23") (pin "7") (pinfunction "PB2_7") (pintype "unspecified"))
      (node (ref "U25") (pin "4") (pinfunction "Q4_4") (pintype "unspecified"))
    )
    (net (code "99") (name "Note_6") (class "Default")
      (node (ref "U22") (pin "7") (pinfunction "PB2_7") (pintype "unspecified"))
      (node (ref "U25") (pin "5") (pinfunction "Q5_5") (pintype "unspecified"))
    )
    (net (code "100") (name "Note_7") (class "Default")
      (node (ref "U25") (pin "6") (pinfunction "Q6_6") (pintype "unspecified"))
      (node (ref "U7") (pin "7") (pinfunction "PB2_7") (pintype "unspecified"))
    )
    (net (code "101") (name "Note_8") (class "Default")
      (node (ref "U25") (pin "7") (pinfunction "Q7_7") (pintype "unspecified"))
      (node (ref "U6") (pin "7") (pinfunction "PB2_7") (pintype "unspecified"))
    )
    (net (code "102") (name "Note_9") (class "Default")
      (node (ref "U10") (pin "7") (pinfunction "PB2_7") (pintype "unspecified"))
      (node (ref "U26") (pin "15") (pinfunction "Q0_15") (pintype "unspecified"))
    )
    (net (code "103") (name "Note_10") (class "Default")
      (node (ref "U11") (pin "7") (pinfunction "PB2_7") (pintype "unspecified"))
      (node (ref "U26") (pin "1") (pinfunction "Q1_1") (pintype "unspecified"))
    )
    (net (code "104") (name "Note_11") (class "Default")
      (node (ref "U18") (pin "7") (pinfunction "PB2_7") (pintype "unspecified"))
      (node (ref "U26") (pin "2") (pinfunction "Q2_2") (pintype "unspecified"))
    )
    (net (code "105") (name "Note_12") (class "Default")
      (node (ref "U19") (pin "7") (pinfunction "PB2_7") (pintype "unspecified"))
      (node (ref "U26") (pin "3") (pinfunction "Q3_3") (pintype "unspecified"))
    )
    (net (code "106") (name "VCC_Bat") (class "Default")
      (node (ref "C1") (pin "2") (pinfunction "2_2") (pintype "unspecified"))
      (node (ref "C11") (pin "2") (pinfunction "2_2") (pintype "unspecified"))
      (node (ref "C13") (pin "2") (pinfunction "2_2") (pintype "unspecified"))
      (node (ref "C15") (pin "2") (pinfunction "2_2") (pintype "unspecified"))
      (node (ref "C17") (pin "2") (pinfunction "2_2") (pintype "unspecified"))
      (node (ref "C19") (pin "2") (pinfunction "2_2") (pintype "unspecified"))
      (node (ref "C21") (pin "2") (pinfunction "2_2") (pintype "unspecified"))
      (node (ref "C23") (pin "2") (pinfunction "2_2") (pintype "unspecified"))
      (node (ref "C26") (pin "2") (pinfunction "2_2") (pintype "unspecified"))
      (node (ref "C29") (pin "1") (pinfunction "1_1") (pintype "unspecified"))
      (node (ref "C3") (pin "2") (pinfunction "2_2") (pintype "unspecified"))
      (node (ref "C30") (pin "1") (pinfunction "1_1") (pintype "unspecified"))
      (node (ref "C5") (pin "2") (pinfunction "2_2") (pintype "unspecified"))
      (node (ref "C7") (pin "2") (pinfunction "2_2") (pintype "unspecified"))
      (node (ref "C9") (pin "2") (pinfunction "2_2") (pintype "unspecified"))
      (node (ref "D1") (pin "1") (pinfunction "1_1") (pintype "unspecified"))
      (node (ref "D10") (pin "1") (pinfunction "1_1") (pintype "unspecified"))
      (node (ref "D11") (pin "1") (pinfunction "1_1") (pintype "unspecified"))
      (node (ref "D12") (pin "1") (pinfunction "1_1") (pintype "unspecified"))
      (node (ref "D2") (pin "1") (pinfunction "1_1") (pintype "unspecified"))
      (node (ref "D3") (pin "1") (pinfunction "1_1") (pintype "unspecified"))
      (node (ref "D4") (pin "1") (pinfunction "1_1") (pintype "unspecified"))
      (node (ref "D5") (pin "1") (pinfunction "1_1") (pintype "unspecified"))
      (node (ref "D6") (pin "1") (pinfunction "1_1") (pintype "unspecified"))
      (node (ref "D7") (pin "1") (pinfunction "1_1") (pintype "unspecified"))
      (node (ref "D8") (pin "1") (pinfunction "1_1") (pintype "unspecified"))
      (node (ref "D9") (pin "1") (pinfunction "1_1") (pintype "unspecified"))
      (node (ref "P1") (pin "2") (pinfunction "2_2") (pintype "unspecified"))
      (node (ref "P10") (pin "2") (pinfunction "2_2") (pintype "unspecified"))
      (node (ref "P11") (pin "2") (pinfunction "2_2") (pintype "unspecified"))
      (node (ref "P12") (pin "2") (pinfunction "2_2") (pintype "unspecified"))
      (node (ref "P13") (pin "1") (pinfunction "1_1") (pintype "unspecified"))
      (node (ref "P2") (pin "2") (pinfunction "2_2") (pintype "unspecified"))
      (node (ref "P3") (pin "2") (pinfunction "2_2") (pintype "unspecified"))
      (node (ref "P4") (pin "2") (pinfunction "2_2") (pintype "unspecified"))
      (node (ref "P5") (pin "2") (pinfunction "2_2") (pintype "unspecified"))
      (node (ref "P6") (pin "2") (pinfunction "2_2") (pintype "unspecified"))
      (node (ref "P7") (pin "2") (pinfunction "2_2") (pintype "unspecified"))
      (node (ref "P8") (pin "2") (pinfunction "2_2") (pintype "unspecified"))
      (node (ref "P9") (pin "2") (pinfunction "2_2") (pintype "unspecified"))
      (node (ref "U1") (pin "1") (pinfunction "IN_1") (pintype "passive"))
      (node (ref "U12") (pin "1") (pinfunction "IN_1") (pintype "passive"))
      (node (ref "U13") (pin "1") (pinfunction "IN_1") (pintype "passive"))
      (node (ref "U16") (pin "1") (pinfunction "IN_1") (pintype "passive"))
      (node (ref "U17") (pin "1") (pinfunction "IN_1") (pintype "passive"))
      (node (ref "U20") (pin "1") (pinfunction "IN_1") (pintype "passive"))
      (node (ref "U21") (pin "1") (pinfunction "IN_1") (pintype "passive"))
      (node (ref "U24") (pin "1") (pinfunction "IN_1") (pintype "passive"))
      (node (ref "U27") (pin "1") (pinfunction "IN_1") (pintype "passive"))
      (node (ref "U4") (pin "1") (pinfunction "IN_1") (pintype "passive"))
      (node (ref "U5") (pin "1") (pinfunction "IN_1") (pintype "passive"))
      (node (ref "U8") (pin "1") (pinfunction "IN_1") (pintype "passive"))
      (node (ref "U9") (pin "1") (pinfunction "IN_1") (pintype "passive"))
    )
    (net (code "107") (name "unconnected-(U26-Q4-Pad4)") (class "Default")
      (node (ref "U26") (pin "4") (pinfunction "Q4_4") (pintype "unspecified+no_connect"))
    )
    (net (code "108") (name "unconnected-(U26-Q5-Pad5)") (class "Default")
      (node (ref "U26") (pin "5") (pinfunction "Q5_5") (pintype "unspecified+no_connect"))
    )
    (net (code "109") (name "unconnected-(U26-Q6-Pad6)") (class "Default")
      (node (ref "U26") (pin "6") (pinfunction "Q6_6") (pintype "unspecified+no_connect"))
    )
    (net (code "110") (name "unconnected-(U26-Q7-Pad7)") (class "Default")
      (node (ref "U26") (pin "7") (pinfunction "Q7_7") (pintype "unspecified+no_connect"))
    )
    (net (code "111") (name "unconnected-(U26-Q7{slash}2-Pad9)") (class "Default")
      (node (ref "U26") (pin "9") (pinfunction "Q7/2_9") (pintype "unspecified+no_connect"))
    )
  )
)
